# HostInterfaceSplitter.net
KiCad netlist of a schematic drawn in EAGLE
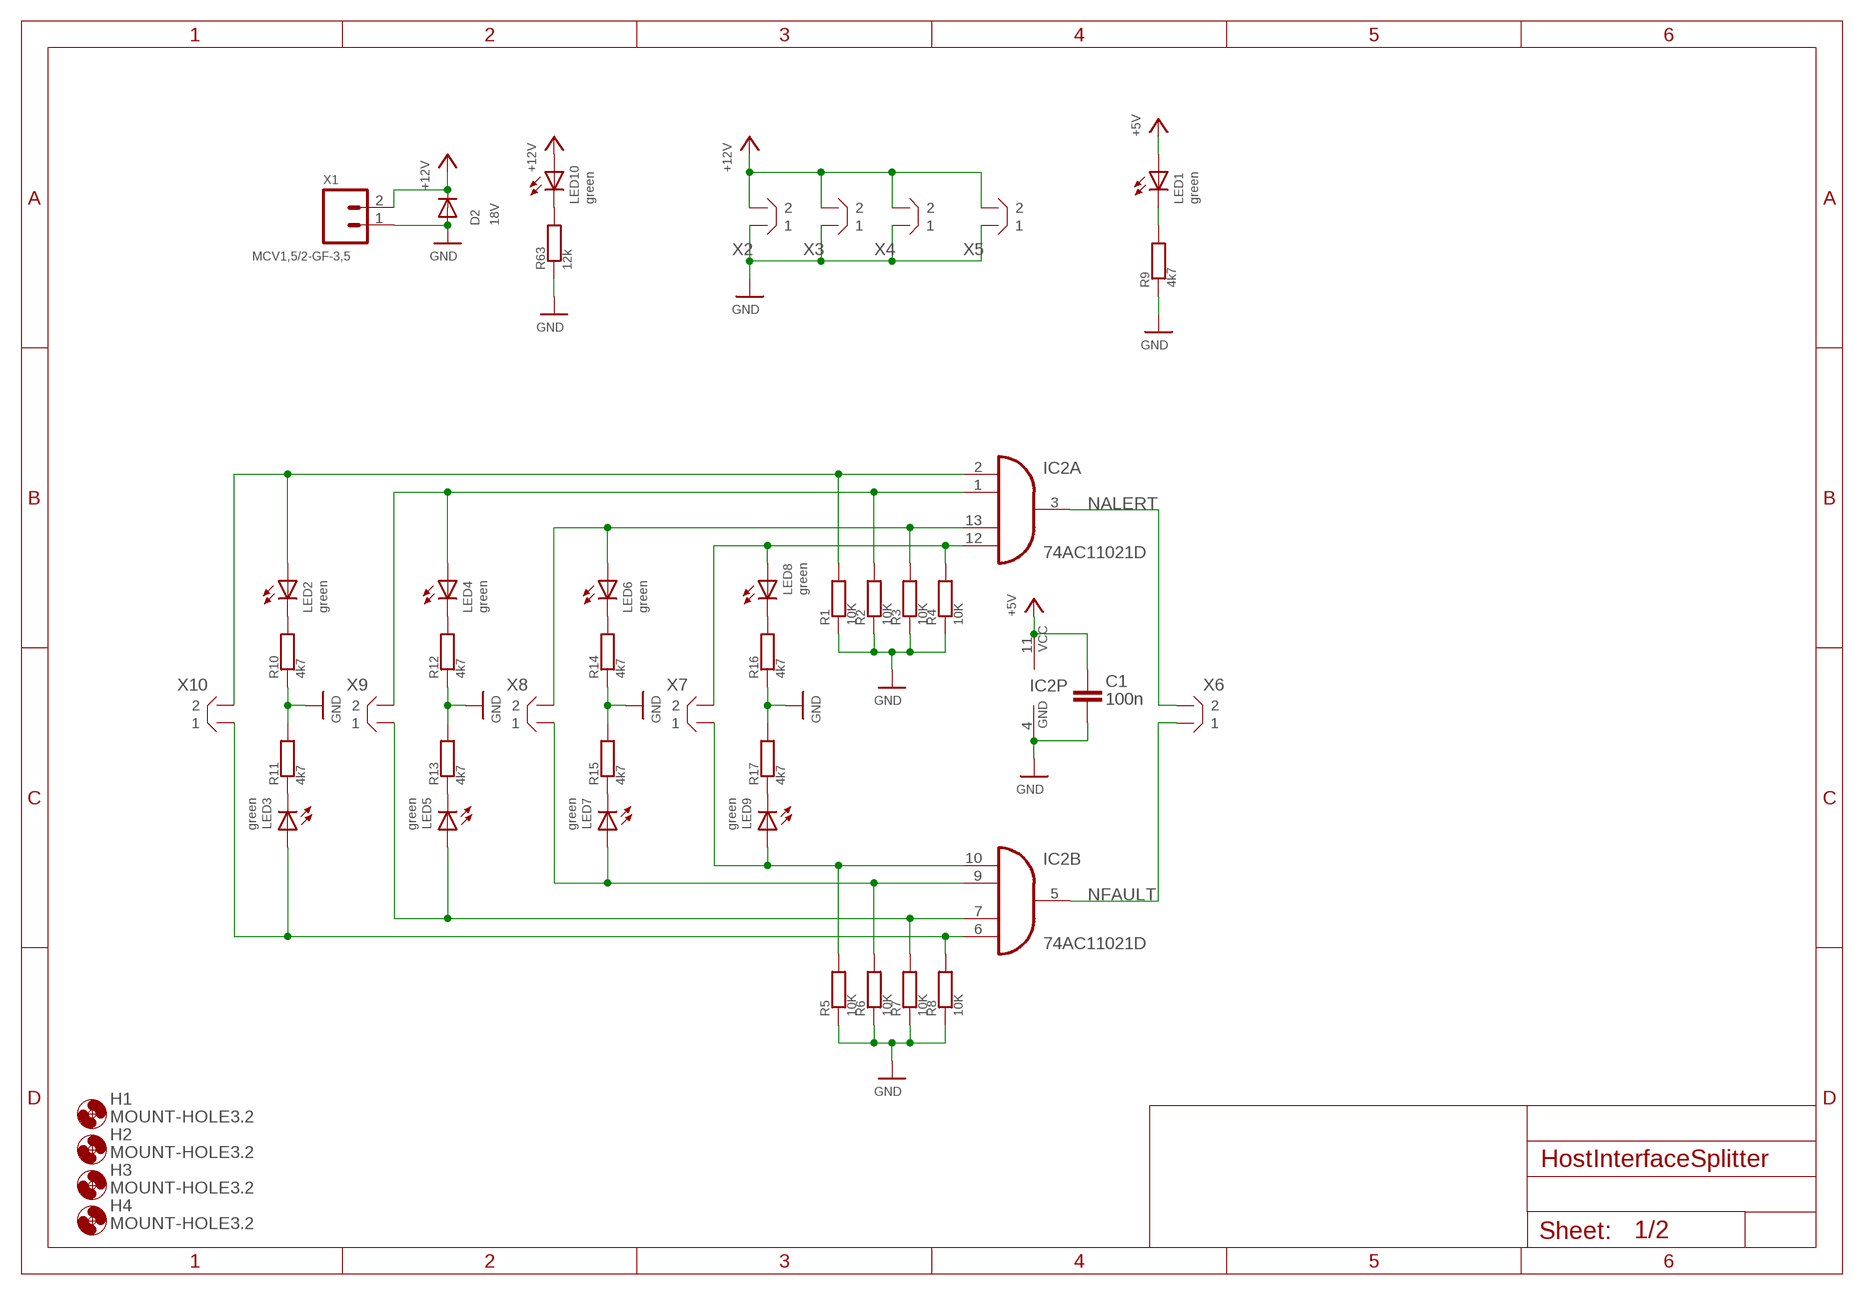
[diagram p0: schematic, sheet 1]
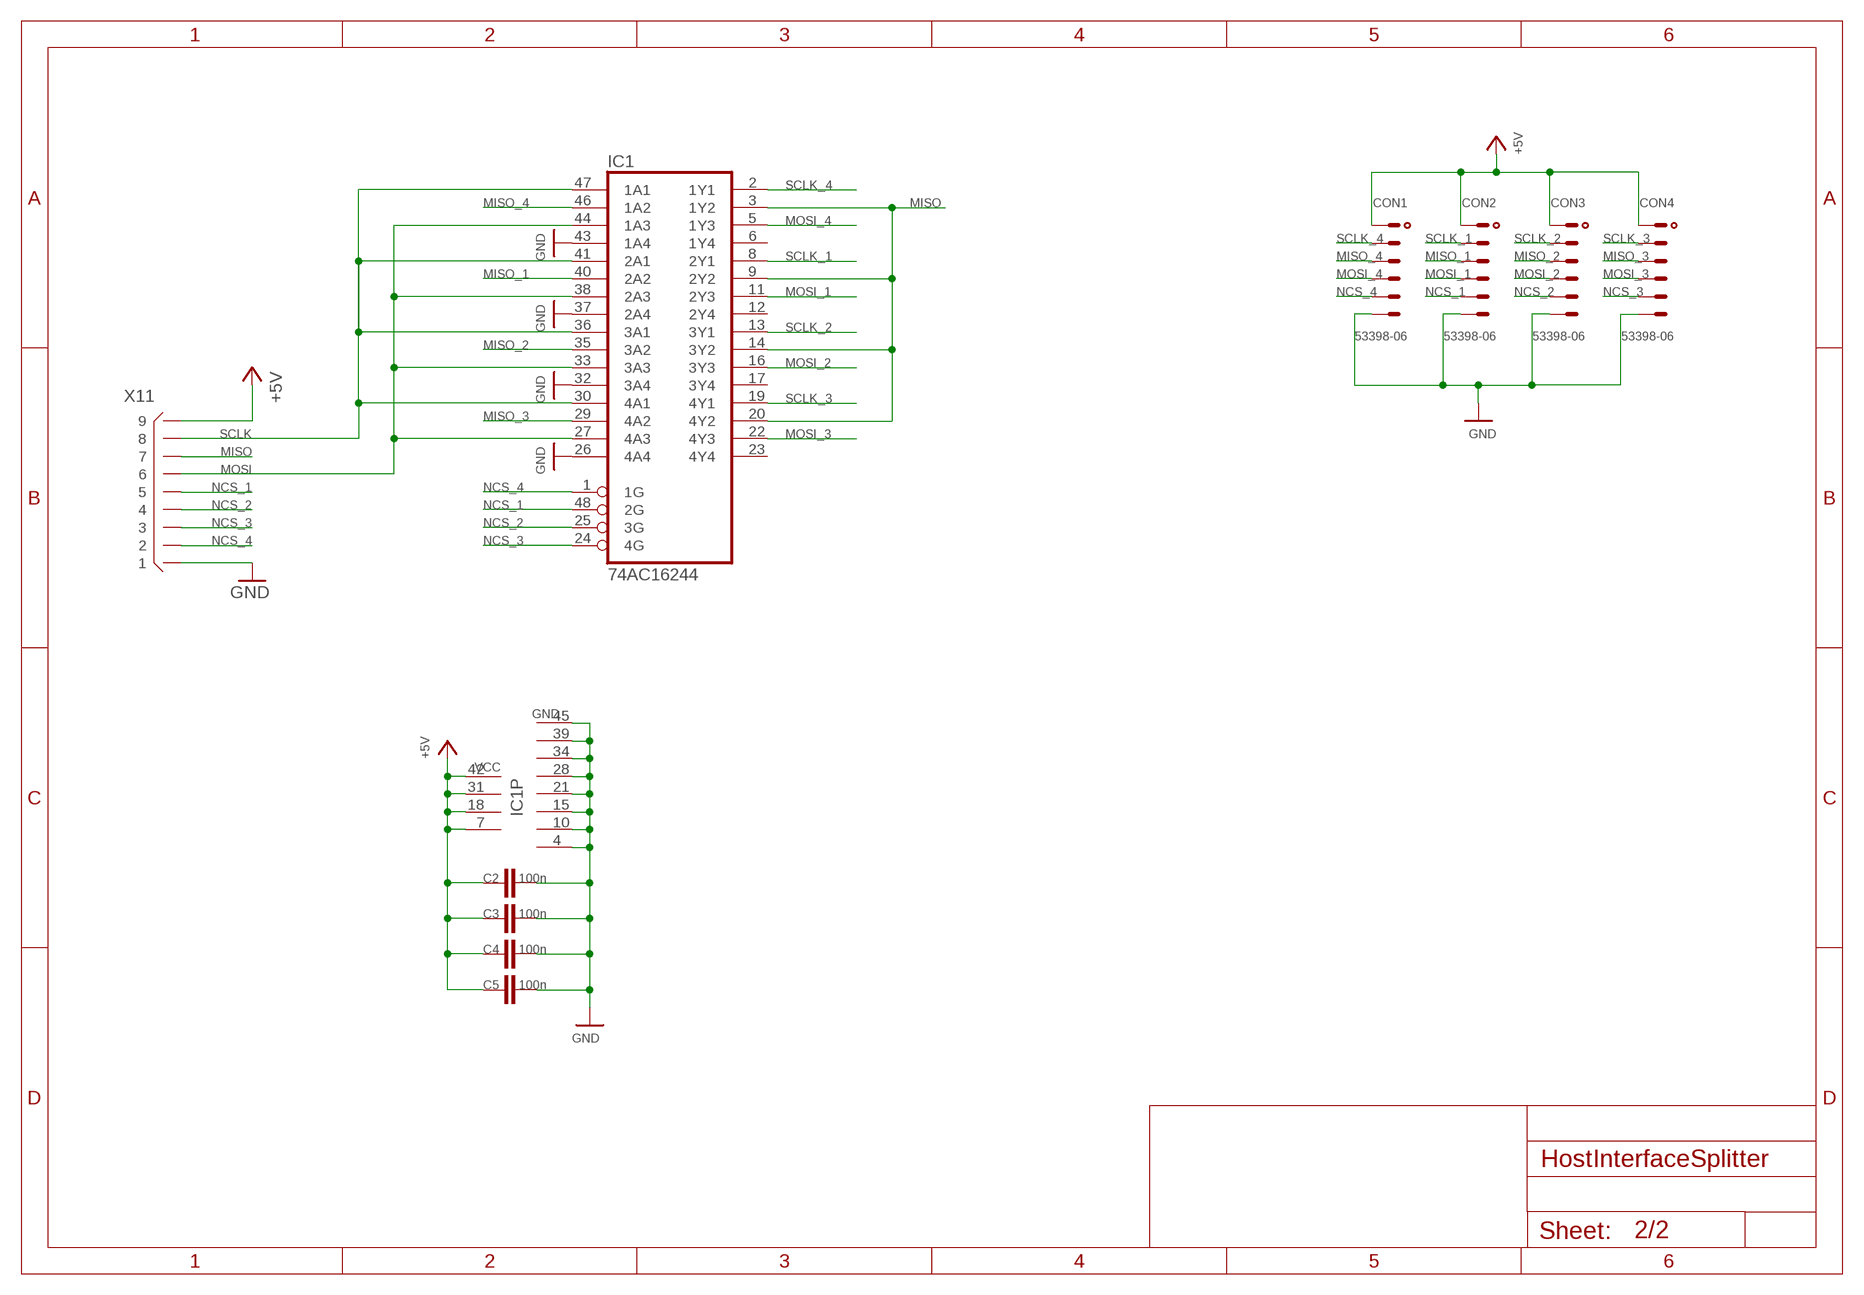
[diagram p1: schematic, sheet 2]

(export (version "E")
  (design (tool "Eeschema 10.0.6"))
  (components
    (comp (ref "C2")
      (value "100n")
      (footprint "eagle-import:C0603")
      (libsource (lib "eagle-import") (part "C0603"))
    )
    (comp (ref "C3")
      (value "100n")
      (footprint "eagle-import:C0603")
      (libsource (lib "eagle-import") (part "C0603"))
    )
    (comp (ref "C4")
      (value "100n")
      (footprint "eagle-import:C0603")
      (libsource (lib "eagle-import") (part "C0603"))
    )
    (comp (ref "C5")
      (value "100n")
      (footprint "eagle-import:C0603")
      (libsource (lib "eagle-import") (part "C0603"))
    )
    (comp (ref "CON1")
      (value "53398-06")
      (footprint "eagle-import:53398-06")
      (libsource (lib "eagle-import") (part "53?-06398"))
    )
    (comp (ref "CON2")
      (value "53398-06")
      (footprint "eagle-import:53398-06")
      (libsource (lib "eagle-import") (part "53?-06398"))
    )
    (comp (ref "CON3")
      (value "53398-06")
      (footprint "eagle-import:53398-06")
      (libsource (lib "eagle-import") (part "53?-06398"))
    )
    (comp (ref "CON4")
      (value "53398-06")
      (footprint "eagle-import:53398-06")
      (libsource (lib "eagle-import") (part "53?-06398"))
    )
    (comp (ref "IC1")
      (value "74AC16244")
      (footprint "eagle-import:SSOP48DL")
      (libsource (lib "eagle-import") (part "74AC16244"))
    )
    (comp (ref "X11")
      (value "B9B-XH")
      (footprint "eagle-import:B9B-XH")
      (libsource (lib "eagle-import") (part "?9B-XHB"))
    )
    (comp (ref "C1")
      (value "100n")
      (footprint "eagle-import:C0603")
      (libsource (lib "eagle-import") (part "C0603"))
    )
    (comp (ref "D2")
      (value "18V")
      (footprint "eagle-import:DO214AA")
      (libsource (lib "eagle-import") (part "DIODE-DO214AA"))
    )
    (comp (ref "H1")
      (value "MOUNT-HOLE3.2")
      (footprint "eagle-import:3,2")
      (libsource (lib "eagle-import") (part "MOUNT-HOLE3.2"))
    )
    (comp (ref "H2")
      (value "MOUNT-HOLE3.2")
      (footprint "eagle-import:3,2")
      (libsource (lib "eagle-import") (part "MOUNT-HOLE3.2"))
    )
    (comp (ref "H3")
      (value "MOUNT-HOLE3.2")
      (footprint "eagle-import:3,2")
      (libsource (lib "eagle-import") (part "MOUNT-HOLE3.2"))
    )
    (comp (ref "H4")
      (value "MOUNT-HOLE3.2")
      (footprint "eagle-import:3,2")
      (libsource (lib "eagle-import") (part "MOUNT-HOLE3.2"))
    )
    (comp (ref "IC2")
      (value "74AC11021D")
      (footprint "eagle-import:SO14")
      (libsource (lib "eagle-import") (part "74AC11021D"))
    )
    (comp (ref "LED1")
      (value "green")
      (footprint "eagle-import:CHIP-LED0805")
      (libsource (lib "eagle-import") (part "LEDCHIP-LED0805"))
    )
    (comp (ref "LED2")
      (value "green")
      (footprint "eagle-import:CHIP-LED0805")
      (libsource (lib "eagle-import") (part "LEDCHIP-LED0805"))
    )
    (comp (ref "LED3")
      (value "green")
      (footprint "eagle-import:CHIP-LED0805")
      (libsource (lib "eagle-import") (part "LEDCHIP-LED0805"))
    )
    (comp (ref "LED4")
      (value "green")
      (footprint "eagle-import:CHIP-LED0805")
      (libsource (lib "eagle-import") (part "LEDCHIP-LED0805"))
    )
    (comp (ref "LED5")
      (value "green")
      (footprint "eagle-import:CHIP-LED0805")
      (libsource (lib "eagle-import") (part "LEDCHIP-LED0805"))
    )
    (comp (ref "LED6")
      (value "green")
      (footprint "eagle-import:CHIP-LED0805")
      (libsource (lib "eagle-import") (part "LEDCHIP-LED0805"))
    )
    (comp (ref "LED7")
      (value "green")
      (footprint "eagle-import:CHIP-LED0805")
      (libsource (lib "eagle-import") (part "LEDCHIP-LED0805"))
    )
    (comp (ref "LED8")
      (value "green")
      (footprint "eagle-import:CHIP-LED0805")
      (libsource (lib "eagle-import") (part "LEDCHIP-LED0805"))
    )
    (comp (ref "LED9")
      (value "green")
      (footprint "eagle-import:CHIP-LED0805")
      (libsource (lib "eagle-import") (part "LEDCHIP-LED0805"))
    )
    (comp (ref "LED10")
      (value "green")
      (footprint "eagle-import:CHIP-LED0805")
      (libsource (lib "eagle-import") (part "LEDCHIP-LED0805"))
    )
    (comp (ref "R1")
      (value "10K")
      (footprint "eagle-import:R0603")
      (libsource (lib "eagle-import") (part "R0603"))
    )
    (comp (ref "R2")
      (value "10K")
      (footprint "eagle-import:R0603")
      (libsource (lib "eagle-import") (part "R0603"))
    )
    (comp (ref "R3")
      (value "10K")
      (footprint "eagle-import:R0603")
      (libsource (lib "eagle-import") (part "R0603"))
    )
    (comp (ref "R4")
      (value "10K")
      (footprint "eagle-import:R0603")
      (libsource (lib "eagle-import") (part "R0603"))
    )
    (comp (ref "R5")
      (value "10K")
      (footprint "eagle-import:R0603")
      (libsource (lib "eagle-import") (part "R0603"))
    )
    (comp (ref "R6")
      (value "10K")
      (footprint "eagle-import:R0603")
      (libsource (lib "eagle-import") (part "R0603"))
    )
    (comp (ref "R7")
      (value "10K")
      (footprint "eagle-import:R0603")
      (libsource (lib "eagle-import") (part "R0603"))
    )
    (comp (ref "R8")
      (value "10K")
      (footprint "eagle-import:R0603")
      (libsource (lib "eagle-import") (part "R0603"))
    )
    (comp (ref "R9")
      (value "4k7")
      (footprint "eagle-import:R0805")
      (libsource (lib "eagle-import") (part "R"))
    )
    (comp (ref "R10")
      (value "4k7")
      (footprint "eagle-import:R0805")
      (libsource (lib "eagle-import") (part "R"))
    )
    (comp (ref "R11")
      (value "4k7")
      (footprint "eagle-import:R0805")
      (libsource (lib "eagle-import") (part "R"))
    )
    (comp (ref "R12")
      (value "4k7")
      (footprint "eagle-import:R0805")
      (libsource (lib "eagle-import") (part "R"))
    )
    (comp (ref "R13")
      (value "4k7")
      (footprint "eagle-import:R0805")
      (libsource (lib "eagle-import") (part "R"))
    )
    (comp (ref "R14")
      (value "4k7")
      (footprint "eagle-import:R0805")
      (libsource (lib "eagle-import") (part "R"))
    )
    (comp (ref "R15")
      (value "4k7")
      (footprint "eagle-import:R0805")
      (libsource (lib "eagle-import") (part "R"))
    )
    (comp (ref "R16")
      (value "4k7")
      (footprint "eagle-import:R0805")
      (libsource (lib "eagle-import") (part "R"))
    )
    (comp (ref "R17")
      (value "4k7")
      (footprint "eagle-import:R0805")
      (libsource (lib "eagle-import") (part "R"))
    )
    (comp (ref "R63")
      (value "12k")
      (footprint "eagle-import:R0805")
      (libsource (lib "eagle-import") (part "R"))
    )
    (comp (ref "X1")
      (value "MCV1,5/2-GF-3,5")
      (footprint "eagle-import:MCV1,5_2-GF-3,5")
      (libsource (lib "eagle-import") (part "MCV1,5/2-GF-3,5"))
    )
    (comp (ref "X2")
      (value "B2B-XH")
      (footprint "eagle-import:B2B-XH")
      (libsource (lib "eagle-import") (part "?2B-XHB"))
    )
    (comp (ref "X3")
      (value "B2B-XH")
      (footprint "eagle-import:B2B-XH")
      (libsource (lib "eagle-import") (part "?2B-XHB"))
    )
    (comp (ref "X4")
      (value "B2B-XH")
      (footprint "eagle-import:B2B-XH")
      (libsource (lib "eagle-import") (part "?2B-XHB"))
    )
    (comp (ref "X5")
      (value "B2B-XH")
      (footprint "eagle-import:B2B-XH")
      (libsource (lib "eagle-import") (part "?2B-XHB"))
    )
    (comp (ref "X6")
      (value "B2B-XH")
      (footprint "eagle-import:B2B-XH")
      (libsource (lib "eagle-import") (part "?2B-XHB"))
    )
    (comp (ref "X7")
      (value "B2B-XH")
      (footprint "eagle-import:B2B-XH")
      (libsource (lib "eagle-import") (part "?2B-XHB"))
    )
    (comp (ref "X8")
      (value "B2B-XH")
      (footprint "eagle-import:B2B-XH")
      (libsource (lib "eagle-import") (part "?2B-XHB"))
    )
    (comp (ref "X9")
      (value "B2B-XH")
      (footprint "eagle-import:B2B-XH")
      (libsource (lib "eagle-import") (part "?2B-XHB"))
    )
    (comp (ref "X10")
      (value "B2B-XH")
      (footprint "eagle-import:B2B-XH")
      (libsource (lib "eagle-import") (part "?2B-XHB"))
    )
  )
  (nets
    (net (code "1") (name "+5V") (class "Default")
      (node (ref "C1") (pin "2") (pinfunction "2_2") (pintype "passive"))
      (node (ref "C2") (pin "2") (pinfunction "2_2") (pintype "passive"))
      (node (ref "C3") (pin "2") (pinfunction "2_2") (pintype "passive"))
      (node (ref "C4") (pin "2") (pinfunction "2_2") (pintype "passive"))
      (node (ref "C5") (pin "2") (pinfunction "2_2") (pintype "passive"))
      (node (ref "CON1") (pin "1") (pinfunction "1_1") (pintype "passive"))
      (node (ref "CON2") (pin "1") (pinfunction "1_1") (pintype "passive"))
      (node (ref "CON3") (pin "1") (pinfunction "1_1") (pintype "passive"))
      (node (ref "CON4") (pin "1") (pinfunction "1_1") (pintype "passive"))
      (node (ref "IC1") (pin "18") (pinfunction "VCC_18") (pintype "power_in"))
      (node (ref "IC1") (pin "31") (pinfunction "VCC_31") (pintype "power_in"))
      (node (ref "IC1") (pin "42") (pinfunction "VCC_42") (pintype "power_in"))
      (node (ref "IC1") (pin "7") (pinfunction "VCC_7") (pintype "power_in"))
      (node (ref "IC2") (pin "11") (pinfunction "VCC_11") (pintype "power_in"))
      (node (ref "LED1") (pin "A") (pinfunction "A_A") (pintype "passive"))
      (node (ref "X11") (pin "P$9") (pinfunction "9_P$9") (pintype "bidirectional"))
    )
    (net (code "2") (name "+12V") (class "Default")
      (node (ref "D2") (pin "C") (pinfunction "C_C") (pintype "passive"))
      (node (ref "LED10") (pin "A") (pinfunction "A_A") (pintype "passive"))
      (node (ref "X1") (pin "2") (pinfunction "2_2") (pintype "passive"))
      (node (ref "X2") (pin "P$2") (pinfunction "2_P$2") (pintype "bidirectional"))
      (node (ref "X3") (pin "P$2") (pinfunction "2_P$2") (pintype "bidirectional"))
      (node (ref "X4") (pin "P$2") (pinfunction "2_P$2") (pintype "bidirectional"))
      (node (ref "X5") (pin "P$2") (pinfunction "2_P$2") (pintype "bidirectional"))
    )
    (net (code "3") (name "GND") (class "Default")
      (node (ref "C1") (pin "1") (pinfunction "1_1") (pintype "passive"))
      (node (ref "C2") (pin "1") (pinfunction "1_1") (pintype "passive"))
      (node (ref "C3") (pin "1") (pinfunction "1_1") (pintype "passive"))
      (node (ref "C4") (pin "1") (pinfunction "1_1") (pintype "passive"))
      (node (ref "C5") (pin "1") (pinfunction "1_1") (pintype "passive"))
      (node (ref "CON1") (pin "6") (pinfunction "6_6") (pintype "passive"))
      (node (ref "CON2") (pin "6") (pinfunction "6_6") (pintype "passive"))
      (node (ref "CON3") (pin "6") (pinfunction "6_6") (pintype "passive"))
      (node (ref "CON4") (pin "6") (pinfunction "6_6") (pintype "passive"))
      (node (ref "D2") (pin "A") (pinfunction "A_A") (pintype "passive"))
      (node (ref "IC1") (pin "10") (pinfunction "GND_10") (pintype "power_in"))
      (node (ref "IC1") (pin "15") (pinfunction "GND_15") (pintype "power_in"))
      (node (ref "IC1") (pin "21") (pinfunction "GND_21") (pintype "power_in"))
      (node (ref "IC1") (pin "26") (pinfunction "4A4_26") (pintype "input"))
      (node (ref "IC1") (pin "28") (pinfunction "GND_28") (pintype "power_in"))
      (node (ref "IC1") (pin "32") (pinfunction "3A4_32") (pintype "input"))
      (node (ref "IC1") (pin "34") (pinfunction "GND_34") (pintype "power_in"))
      (node (ref "IC1") (pin "37") (pinfunction "2A4_37") (pintype "input"))
      (node (ref "IC1") (pin "39") (pinfunction "GND_39") (pintype "power_in"))
      (node (ref "IC1") (pin "4") (pinfunction "GND_4") (pintype "power_in"))
      (node (ref "IC1") (pin "43") (pinfunction "1A4_43") (pintype "input"))
      (node (ref "IC1") (pin "45") (pinfunction "GND_45") (pintype "power_in"))
      (node (ref "IC2") (pin "4") (pinfunction "GND_4") (pintype "power_in"))
      (node (ref "R1") (pin "1") (pinfunction "1_1") (pintype "passive"))
      (node (ref "R10") (pin "1") (pinfunction "1_1") (pintype "passive"))
      (node (ref "R11") (pin "2") (pinfunction "2_2") (pintype "passive"))
      (node (ref "R12") (pin "1") (pinfunction "1_1") (pintype "passive"))
      (node (ref "R13") (pin "2") (pinfunction "2_2") (pintype "passive"))
      (node (ref "R14") (pin "1") (pinfunction "1_1") (pintype "passive"))
      (node (ref "R15") (pin "2") (pinfunction "2_2") (pintype "passive"))
      (node (ref "R16") (pin "1") (pinfunction "1_1") (pintype "passive"))
      (node (ref "R17") (pin "2") (pinfunction "2_2") (pintype "passive"))
      (node (ref "R2") (pin "1") (pinfunction "1_1") (pintype "passive"))
      (node (ref "R3") (pin "1") (pinfunction "1_1") (pintype "passive"))
      (node (ref "R4") (pin "1") (pinfunction "1_1") (pintype "passive"))
      (node (ref "R5") (pin "1") (pinfunction "1_1") (pintype "passive"))
      (node (ref "R6") (pin "1") (pinfunction "1_1") (pintype "passive"))
      (node (ref "R63") (pin "1") (pinfunction "1_1") (pintype "passive"))
      (node (ref "R7") (pin "1") (pinfunction "1_1") (pintype "passive"))
      (node (ref "R8") (pin "1") (pinfunction "1_1") (pintype "passive"))
      (node (ref "R9") (pin "1") (pinfunction "1_1") (pintype "passive"))
      (node (ref "X1") (pin "1") (pinfunction "1_1") (pintype "passive"))
      (node (ref "X11") (pin "P$1") (pinfunction "1_P$1") (pintype "bidirectional"))
      (node (ref "X2") (pin "P$1") (pinfunction "1_P$1") (pintype "bidirectional"))
      (node (ref "X3") (pin "P$1") (pinfunction "1_P$1") (pintype "bidirectional"))
      (node (ref "X4") (pin "P$1") (pinfunction "1_P$1") (pintype "bidirectional"))
      (node (ref "X5") (pin "P$1") (pinfunction "1_P$1") (pintype "bidirectional"))
    )
    (net (code "4") (name "MISO") (class "Default")
      (node (ref "IC1") (pin "14") (pinfunction "3Y2_14") (pintype "tri_state"))
      (node (ref "IC1") (pin "20") (pinfunction "4Y2_20") (pintype "tri_state"))
      (node (ref "IC1") (pin "3") (pinfunction "1Y2_3") (pintype "tri_state"))
      (node (ref "IC1") (pin "9") (pinfunction "2Y2_9") (pintype "tri_state"))
      (node (ref "X11") (pin "P$7") (pinfunction "7_P$7") (pintype "bidirectional"))
    )
    (net (code "5") (name "MISO_1") (class "Default")
      (node (ref "CON2") (pin "3") (pinfunction "3_3") (pintype "passive"))
      (node (ref "IC1") (pin "40") (pinfunction "2A2_40") (pintype "input"))
    )
    (net (code "6") (name "MISO_2") (class "Default")
      (node (ref "CON3") (pin "3") (pinfunction "3_3") (pintype "passive"))
      (node (ref "IC1") (pin "35") (pinfunction "3A2_35") (pintype "input"))
    )
    (net (code "7") (name "MISO_3") (class "Default")
      (node (ref "CON4") (pin "3") (pinfunction "3_3") (pintype "passive"))
      (node (ref "IC1") (pin "29") (pinfunction "4A2_29") (pintype "input"))
    )
    (net (code "8") (name "MISO_4") (class "Default")
      (node (ref "CON1") (pin "3") (pinfunction "3_3") (pintype "passive"))
      (node (ref "IC1") (pin "46") (pinfunction "1A2_46") (pintype "input"))
    )
    (net (code "9") (name "MOSI") (class "Default")
      (node (ref "IC1") (pin "27") (pinfunction "4A3_27") (pintype "input"))
      (node (ref "IC1") (pin "33") (pinfunction "3A3_33") (pintype "input"))
      (node (ref "IC1") (pin "38") (pinfunction "2A3_38") (pintype "input"))
      (node (ref "IC1") (pin "44") (pinfunction "1A3_44") (pintype "input"))
      (node (ref "X11") (pin "P$6") (pinfunction "6_P$6") (pintype "bidirectional"))
    )
    (net (code "10") (name "MOSI_1") (class "Default")
      (node (ref "CON2") (pin "4") (pinfunction "4_4") (pintype "passive"))
      (node (ref "IC1") (pin "11") (pinfunction "2Y3_11") (pintype "tri_state"))
    )
    (net (code "11") (name "MOSI_2") (class "Default")
      (node (ref "CON3") (pin "4") (pinfunction "4_4") (pintype "passive"))
      (node (ref "IC1") (pin "16") (pinfunction "3Y3_16") (pintype "tri_state"))
    )
    (net (code "12") (name "MOSI_3") (class "Default")
      (node (ref "CON4") (pin "4") (pinfunction "4_4") (pintype "passive"))
      (node (ref "IC1") (pin "22") (pinfunction "4Y3_22") (pintype "tri_state"))
    )
    (net (code "13") (name "MOSI_4") (class "Default")
      (node (ref "CON1") (pin "4") (pinfunction "4_4") (pintype "passive"))
      (node (ref "IC1") (pin "5") (pinfunction "1Y3_5") (pintype "tri_state"))
    )
    (net (code "14") (name "NALERT") (class "Default")
      (node (ref "IC2") (pin "3") (pinfunction "O_3") (pintype "output"))
      (node (ref "X6") (pin "P$2") (pinfunction "2_P$2") (pintype "bidirectional"))
    )
    (net (code "15") (name "NCS_1") (class "Default")
      (node (ref "CON2") (pin "5") (pinfunction "5_5") (pintype "passive"))
      (node (ref "IC1") (pin "48") (pinfunction "2G_48") (pintype "input"))
      (node (ref "X11") (pin "P$5") (pinfunction "5_P$5") (pintype "bidirectional"))
    )
    (net (code "16") (name "NCS_2") (class "Default")
      (node (ref "CON3") (pin "5") (pinfunction "5_5") (pintype "passive"))
      (node (ref "IC1") (pin "25") (pinfunction "3G_25") (pintype "input"))
      (node (ref "X11") (pin "P$4") (pinfunction "4_P$4") (pintype "bidirectional"))
    )
    (net (code "17") (name "NCS_3") (class "Default")
      (node (ref "CON4") (pin "5") (pinfunction "5_5") (pintype "passive"))
      (node (ref "IC1") (pin "24") (pinfunction "4G_24") (pintype "input"))
      (node (ref "X11") (pin "P$3") (pinfunction "3_P$3") (pintype "bidirectional"))
    )
    (net (code "18") (name "NCS_4") (class "Default")
      (node (ref "CON1") (pin "5") (pinfunction "5_5") (pintype "passive"))
      (node (ref "IC1") (pin "1") (pinfunction "1G_1") (pintype "input"))
      (node (ref "X11") (pin "P$2") (pinfunction "2_P$2") (pintype "bidirectional"))
    )
    (net (code "19") (name "NFAULT") (class "Default")
      (node (ref "IC2") (pin "5") (pinfunction "O_5") (pintype "output"))
      (node (ref "X6") (pin "P$1") (pinfunction "1_P$1") (pintype "bidirectional"))
    )
    (net (code "20") (name "Net-(IC2A-I0)") (class "Default")
      (node (ref "IC2") (pin "2") (pinfunction "I0_2") (pintype "input"))
      (node (ref "LED2") (pin "A") (pinfunction "A_A") (pintype "passive"))
      (node (ref "R1") (pin "2") (pinfunction "2_2") (pintype "passive"))
      (node (ref "X10") (pin "P$2") (pinfunction "2_P$2") (pintype "bidirectional"))
    )
    (net (code "21") (name "Net-(IC2A-I1)") (class "Default")
      (node (ref "IC2") (pin "1") (pinfunction "I1_1") (pintype "input"))
      (node (ref "LED4") (pin "A") (pinfunction "A_A") (pintype "passive"))
      (node (ref "R2") (pin "2") (pinfunction "2_2") (pintype "passive"))
      (node (ref "X9") (pin "P$2") (pinfunction "2_P$2") (pintype "bidirectional"))
    )
    (net (code "22") (name "Net-(IC2A-I2)") (class "Default")
      (node (ref "IC2") (pin "13") (pinfunction "I2_13") (pintype "input"))
      (node (ref "LED6") (pin "A") (pinfunction "A_A") (pintype "passive"))
      (node (ref "R3") (pin "2") (pinfunction "2_2") (pintype "passive"))
      (node (ref "X8") (pin "P$2") (pinfunction "2_P$2") (pintype "bidirectional"))
    )
    (net (code "23") (name "Net-(IC2A-I3)") (class "Default")
      (node (ref "IC2") (pin "12") (pinfunction "I3_12") (pintype "input"))
      (node (ref "LED8") (pin "A") (pinfunction "A_A") (pintype "passive"))
      (node (ref "R4") (pin "2") (pinfunction "2_2") (pintype "passive"))
      (node (ref "X7") (pin "P$2") (pinfunction "2_P$2") (pintype "bidirectional"))
    )
    (net (code "24") (name "Net-(IC2B-I0)") (class "Default")
      (node (ref "IC2") (pin "10") (pinfunction "I0_10") (pintype "input"))
      (node (ref "LED9") (pin "A") (pinfunction "A_A") (pintype "passive"))
      (node (ref "R5") (pin "2") (pinfunction "2_2") (pintype "passive"))
      (node (ref "X7") (pin "P$1") (pinfunction "1_P$1") (pintype "bidirectional"))
    )
    (net (code "25") (name "Net-(IC2B-I1)") (class "Default")
      (node (ref "IC2") (pin "9") (pinfunction "I1_9") (pintype "input"))
      (node (ref "LED7") (pin "A") (pinfunction "A_A") (pintype "passive"))
      (node (ref "R6") (pin "2") (pinfunction "2_2") (pintype "passive"))
      (node (ref "X8") (pin "P$1") (pinfunction "1_P$1") (pintype "bidirectional"))
    )
    (net (code "26") (name "Net-(IC2B-I2)") (class "Default")
      (node (ref "IC2") (pin "7") (pinfunction "I2_7") (pintype "input"))
      (node (ref "LED5") (pin "A") (pinfunction "A_A") (pintype "passive"))
      (node (ref "R7") (pin "2") (pinfunction "2_2") (pintype "passive"))
      (node (ref "X9") (pin "P$1") (pinfunction "1_P$1") (pintype "bidirectional"))
    )
    (net (code "27") (name "Net-(IC2B-I3)") (class "Default")
      (node (ref "IC2") (pin "6") (pinfunction "I3_6") (pintype "input"))
      (node (ref "LED3") (pin "A") (pinfunction "A_A") (pintype "passive"))
      (node (ref "R8") (pin "2") (pinfunction "2_2") (pintype "passive"))
      (node (ref "X10") (pin "P$1") (pinfunction "1_P$1") (pintype "bidirectional"))
    )
    (net (code "28") (name "Net-(LED1-PadC)") (class "Default")
      (node (ref "LED1") (pin "C") (pinfunction "C_C") (pintype "passive"))
      (node (ref "R9") (pin "2") (pinfunction "2_2") (pintype "passive"))
    )
    (net (code "29") (name "Net-(LED2-PadC)") (class "Default")
      (node (ref "LED2") (pin "C") (pinfunction "C_C") (pintype "passive"))
      (node (ref "R10") (pin "2") (pinfunction "2_2") (pintype "passive"))
    )
    (net (code "30") (name "Net-(LED3-PadC)") (class "Default")
      (node (ref "LED3") (pin "C") (pinfunction "C_C") (pintype "passive"))
      (node (ref "R11") (pin "1") (pinfunction "1_1") (pintype "passive"))
    )
    (net (code "31") (name "Net-(LED4-PadC)") (class "Default")
      (node (ref "LED4") (pin "C") (pinfunction "C_C") (pintype "passive"))
      (node (ref "R12") (pin "2") (pinfunction "2_2") (pintype "passive"))
    )
    (net (code "32") (name "Net-(LED5-PadC)") (class "Default")
      (node (ref "LED5") (pin "C") (pinfunction "C_C") (pintype "passive"))
      (node (ref "R13") (pin "1") (pinfunction "1_1") (pintype "passive"))
    )
    (net (code "33") (name "Net-(LED6-PadC)") (class "Default")
      (node (ref "LED6") (pin "C") (pinfunction "C_C") (pintype "passive"))
      (node (ref "R14") (pin "2") (pinfunction "2_2") (pintype "passive"))
    )
    (net (code "34") (name "Net-(LED7-PadC)") (class "Default")
      (node (ref "LED7") (pin "C") (pinfunction "C_C") (pintype "passive"))
      (node (ref "R15") (pin "1") (pinfunction "1_1") (pintype "passive"))
    )
    (net (code "35") (name "Net-(LED8-PadC)") (class "Default")
      (node (ref "LED8") (pin "C") (pinfunction "C_C") (pintype "passive"))
      (node (ref "R16") (pin "2") (pinfunction "2_2") (pintype "passive"))
    )
    (net (code "36") (name "Net-(LED9-PadC)") (class "Default")
      (node (ref "LED9") (pin "C") (pinfunction "C_C") (pintype "passive"))
      (node (ref "R17") (pin "1") (pinfunction "1_1") (pintype "passive"))
    )
    (net (code "37") (name "Net-(LED10-PadC)") (class "Default")
      (node (ref "LED10") (pin "C") (pinfunction "C_C") (pintype "passive"))
      (node (ref "R63") (pin "2") (pinfunction "2_2") (pintype "passive"))
    )
    (net (code "38") (name "SCLK") (class "Default")
      (node (ref "IC1") (pin "30") (pinfunction "4A1_30") (pintype "input"))
      (node (ref "IC1") (pin "36") (pinfunction "3A1_36") (pintype "input"))
      (node (ref "IC1") (pin "41") (pinfunction "2A1_41") (pintype "input"))
      (node (ref "IC1") (pin "47") (pinfunction "1A1_47") (pintype "input"))
      (node (ref "X11") (pin "P$8") (pinfunction "8_P$8") (pintype "bidirectional"))
    )
    (net (code "39") (name "SCLK_1") (class "Default")
      (node (ref "CON2") (pin "2") (pinfunction "2_2") (pintype "passive"))
      (node (ref "IC1") (pin "8") (pinfunction "2Y1_8") (pintype "tri_state"))
    )
    (net (code "40") (name "SCLK_2") (class "Default")
      (node (ref "CON3") (pin "2") (pinfunction "2_2") (pintype "passive"))
      (node (ref "IC1") (pin "13") (pinfunction "3Y1_13") (pintype "tri_state"))
    )
    (net (code "41") (name "SCLK_3") (class "Default")
      (node (ref "CON4") (pin "2") (pinfunction "2_2") (pintype "passive"))
      (node (ref "IC1") (pin "19") (pinfunction "4Y1_19") (pintype "tri_state"))
    )
    (net (code "42") (name "SCLK_4") (class "Default")
      (node (ref "CON1") (pin "2") (pinfunction "2_2") (pintype "passive"))
      (node (ref "IC1") (pin "2") (pinfunction "1Y1_2") (pintype "tri_state"))
    )
    (net (code "43") (name "unconnected-(IC1A-1Y4-Pad6)") (class "Default")
      (node (ref "IC1") (pin "6") (pinfunction "1Y4_6") (pintype "tri_state"))
    )
    (net (code "44") (name "unconnected-(IC1A-2Y4-Pad12)") (class "Default")
      (node (ref "IC1") (pin "12") (pinfunction "2Y4_12") (pintype "tri_state"))
    )
    (net (code "45") (name "unconnected-(IC1A-3Y4-Pad17)") (class "Default")
      (node (ref "IC1") (pin "17") (pinfunction "3Y4_17") (pintype "tri_state"))
    )
    (net (code "46") (name "unconnected-(IC1A-4Y4-Pad23)") (class "Default")
      (node (ref "IC1") (pin "23") (pinfunction "4Y4_23") (pintype "tri_state"))
    )
  )
)
